# sheet2_sensors.net
KiCad netlist of a schematic drawn in Altium Designer
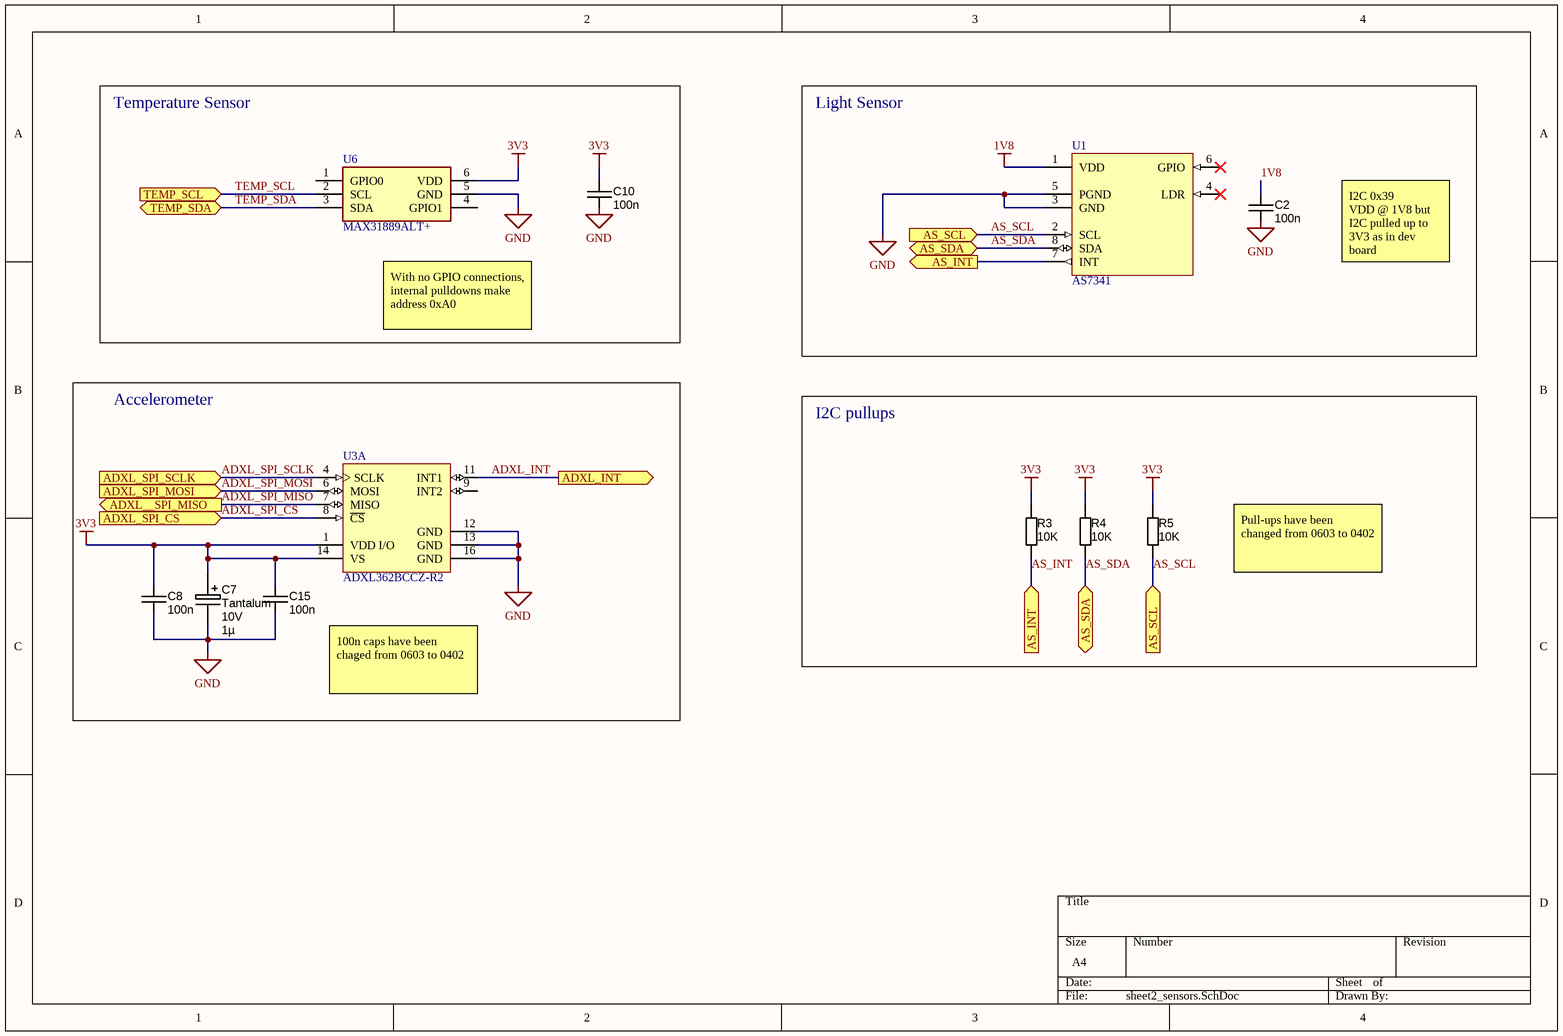
[diagram p0: sheet2_sensors.SchDoc]

(export (version "E")
  (design (tool "Eeschema 10.0.6"))
  (components
    (comp (ref "C2")
      (value "100n")
      (footprint "CAPC1005X55N")
      (description "Capacitor SMD Cer 100nF 10% 16V X5R 0402")
      (fields (field (name "TOLERANCE") "±10%"))
      (libsource (lib "Libs_RRutledge") (part "CAPC_100n_0402_X5R_16V_10%"))
    )
    (comp (ref "C7")
      (value "1µ")
      (footprint "CAPMP2012X150USR")
      (description "Capacitor SMD Tantalum 1uF 20% 10V 0805")
      (fields
        (field (name "TOLERANCE") "±20%")
        (field (name "MATERIAL") "Tantalum")
        (field (name "RATINGS") "10V")
      )
      (libsource (lib "Libs_RRutledge") (part "CAPT_1u_0805_10V"))
    )
    (comp (ref "C8")
      (value "100n")
      (footprint "CAPC1005X55N")
      (description "Capacitor SMD Cer 100nF 10% 16V X5R 0402")
      (fields (field (name "TOLERANCE") "±10%"))
      (libsource (lib "Libs_RRutledge") (part "CAPC_100n_0402_X5R_16V_10%"))
    )
    (comp (ref "C10")
      (value "100n")
      (footprint "CAPC1005X55N")
      (description "Capacitor SMD Cer 100nF 10% 16V X5R 0402")
      (fields (field (name "TOLERANCE") "±10%"))
      (libsource (lib "Libs_RRutledge") (part "CAPC_100n_0402_X5R_16V_10%"))
    )
    (comp (ref "C15")
      (value "100n")
      (footprint "CAPC1005X55N")
      (description "Capacitor SMD Cer 100nF 10% 16V X5R 0402")
      (fields (field (name "TOLERANCE") "±10%"))
      (libsource (lib "Libs_RRutledge") (part "CAPC_100n_0402_X5R_16V_10%"))
    )
    (comp (ref "R3")
      (value "10K")
      (footprint "RESC1005X40N")
      (description "Resistor SMD chip 10k Ohm 0.063W 5% 0402")
      (fields (field (name "TOLERANCE") "±5%") (field (name "Comment") "Thick Film"))
      (libsource (lib "Libs_RRutledge") (part "RES_10K_0402_5%"))
    )
    (comp (ref "R4")
      (value "10K")
      (footprint "RESC1005X40N")
      (description "Resistor SMD chip 10k Ohm 0.063W 5% 0402")
      (fields (field (name "TOLERANCE") "±5%") (field (name "Comment") "Thick Film"))
      (libsource (lib "Libs_RRutledge") (part "RES_10K_0402_5%"))
    )
    (comp (ref "R5")
      (value "10K")
      (footprint "RESC1005X40N")
      (description "Resistor SMD chip 10k Ohm 0.063W 5% 0402")
      (fields (field (name "TOLERANCE") "±5%") (field (name "Comment") "Thick Film"))
      (libsource (lib "Libs_RRutledge") (part "RES_10K_0402_5%"))
    )
    (comp (ref "U1")
      (value "AS7341")
      (footprint "OLGA8")
      (description "AMS AS7341\r\n11-Channel Spectral Sensor Frontend")
      (libsource (lib "Light Sensor Prototype") (part "AS7341"))
    )
    (comp (ref "U3")
      (value "ADXL362BCCZ-R2")
      (footprint "ADI-CC-16-4_N")
      (fields (field (name "MANUFACTURER") "Analog Devices"))
      (libsource (lib "Analog Devices MEMS Inertial Sensors") (part "ADXL362BCCZ-R2"))
    )
    (comp (ref "U6")
      (value "MAX31889ALT+")
      (footprint "SamacSys:MAX31889ALT")
      (description "Integrated Circuit")
      (libsource (lib "*") (part "MAX31889ALT+"))
    )
  )
  (nets
    (net (code "1") (name "/ADXL_INT") (class "Default")
      (node (ref "U3") (pin "11") (pinfunction "INT1_11") (pintype "bidirectional"))
    )
    (net (code "2") (name "/ADXL_SPI_CS") (class "Default")
      (node (ref "U3") (pin "8") (pinfunction "~{CS}_8") (pintype "input"))
    )
    (net (code "3") (name "/ADXL_SPI_MISO") (class "Default")
      (node (ref "U3") (pin "7") (pinfunction "MISO_7") (pintype "bidirectional"))
    )
    (net (code "4") (name "/ADXL_SPI_MOSI") (class "Default")
      (node (ref "U3") (pin "6") (pinfunction "MOSI_6") (pintype "bidirectional"))
    )
    (net (code "5") (name "/ADXL_SPI_SCLK") (class "Default")
      (node (ref "U3") (pin "4") (pinfunction "SCLK_4") (pintype "input"))
    )
    (net (code "6") (name "/AS_INT") (class "Default")
      (node (ref "R3") (pin "2") (pinfunction "2_2") (pintype "passive"))
      (node (ref "U1") (pin "7") (pinfunction "INT_7") (pintype "output"))
    )
    (net (code "7") (name "/AS_SCL") (class "Default")
      (node (ref "R5") (pin "2") (pinfunction "2_2") (pintype "passive"))
      (node (ref "U1") (pin "2") (pinfunction "SCL_2") (pintype "input"))
    )
    (net (code "8") (name "/AS_SDA") (class "Default")
      (node (ref "R4") (pin "2") (pinfunction "2_2") (pintype "passive"))
      (node (ref "U1") (pin "8") (pinfunction "SDA_8") (pintype "bidirectional"))
    )
    (net (code "9") (name "/TEMP_SCL") (class "Default")
      (node (ref "U6") (pin "2") (pinfunction "SCL_2") (pintype "passive"))
    )
    (net (code "10") (name "/TEMP_SDA") (class "Default")
      (node (ref "U6") (pin "3") (pinfunction "SDA_3") (pintype "passive"))
    )
    (net (code "11") (name "1V8") (class "Default")
      (node (ref "C2") (pin "1") (pintype "passive"))
      (node (ref "U1") (pin "1") (pinfunction "VDD_1") (pintype "power_in"))
    )
    (net (code "12") (name "3V3") (class "Default")
      (node (ref "C10") (pin "1") (pintype "passive"))
      (node (ref "C15") (pin "1") (pintype "passive"))
      (node (ref "C7") (pin "1") (pintype "passive"))
      (node (ref "C8") (pin "1") (pintype "passive"))
      (node (ref "R3") (pin "1") (pinfunction "1_1") (pintype "passive"))
      (node (ref "R4") (pin "1") (pinfunction "1_1") (pintype "passive"))
      (node (ref "R5") (pin "1") (pinfunction "1_1") (pintype "passive"))
      (node (ref "U3") (pin "1") (pinfunction "VDD_I/O_1") (pintype "power_in"))
      (node (ref "U3") (pin "14") (pinfunction "VS_14") (pintype "power_in"))
      (node (ref "U6") (pin "6") (pinfunction "VDD_6") (pintype "passive"))
    )
    (net (code "13") (name "GND") (class "Default")
      (node (ref "C10") (pin "2") (pintype "passive"))
      (node (ref "C15") (pin "2") (pintype "passive"))
      (node (ref "C2") (pin "2") (pintype "passive"))
      (node (ref "C7") (pin "2") (pintype "passive"))
      (node (ref "C8") (pin "2") (pintype "passive"))
      (node (ref "U1") (pin "3") (pinfunction "GND_3") (pintype "power_in"))
      (node (ref "U1") (pin "5") (pinfunction "PGND_5") (pintype "power_in"))
      (node (ref "U3") (pin "12") (pinfunction "GND_12") (pintype "power_in"))
      (node (ref "U3") (pin "13") (pinfunction "GND_13") (pintype "power_in"))
      (node (ref "U3") (pin "16") (pinfunction "GND_16") (pintype "power_in"))
      (node (ref "U6") (pin "5") (pinfunction "GND_5") (pintype "passive"))
    )
    (net (code "14") (name "unconnected-(U1-GPIO-Pad6)") (class "Default")
      (node (ref "U1") (pin "6") (pinfunction "GPIO_6") (pintype "input+no_connect"))
    )
    (net (code "15") (name "unconnected-(U1-LDR-Pad4)") (class "Default")
      (node (ref "U1") (pin "4") (pinfunction "LDR_4") (pintype "input+no_connect"))
    )
    (net (code "16") (name "unconnected-(U3A-INT2-Pad9)") (class "Default")
      (node (ref "U3") (pin "9") (pinfunction "INT2_9") (pintype "bidirectional"))
    )
    (net (code "17") (name "unconnected-(U6-GPIO0-Pad1)") (class "Default")
      (node (ref "U6") (pin "1") (pinfunction "GPIO0_1") (pintype "passive"))
    )
    (net (code "18") (name "unconnected-(U6-GPIO1-Pad4)") (class "Default")
      (node (ref "U6") (pin "4") (pinfunction "GPIO1_4") (pintype "passive"))
    )
  )
)
